# Variable_and_Constant.net
KiCad netlist of a schematic drawn in EAGLE
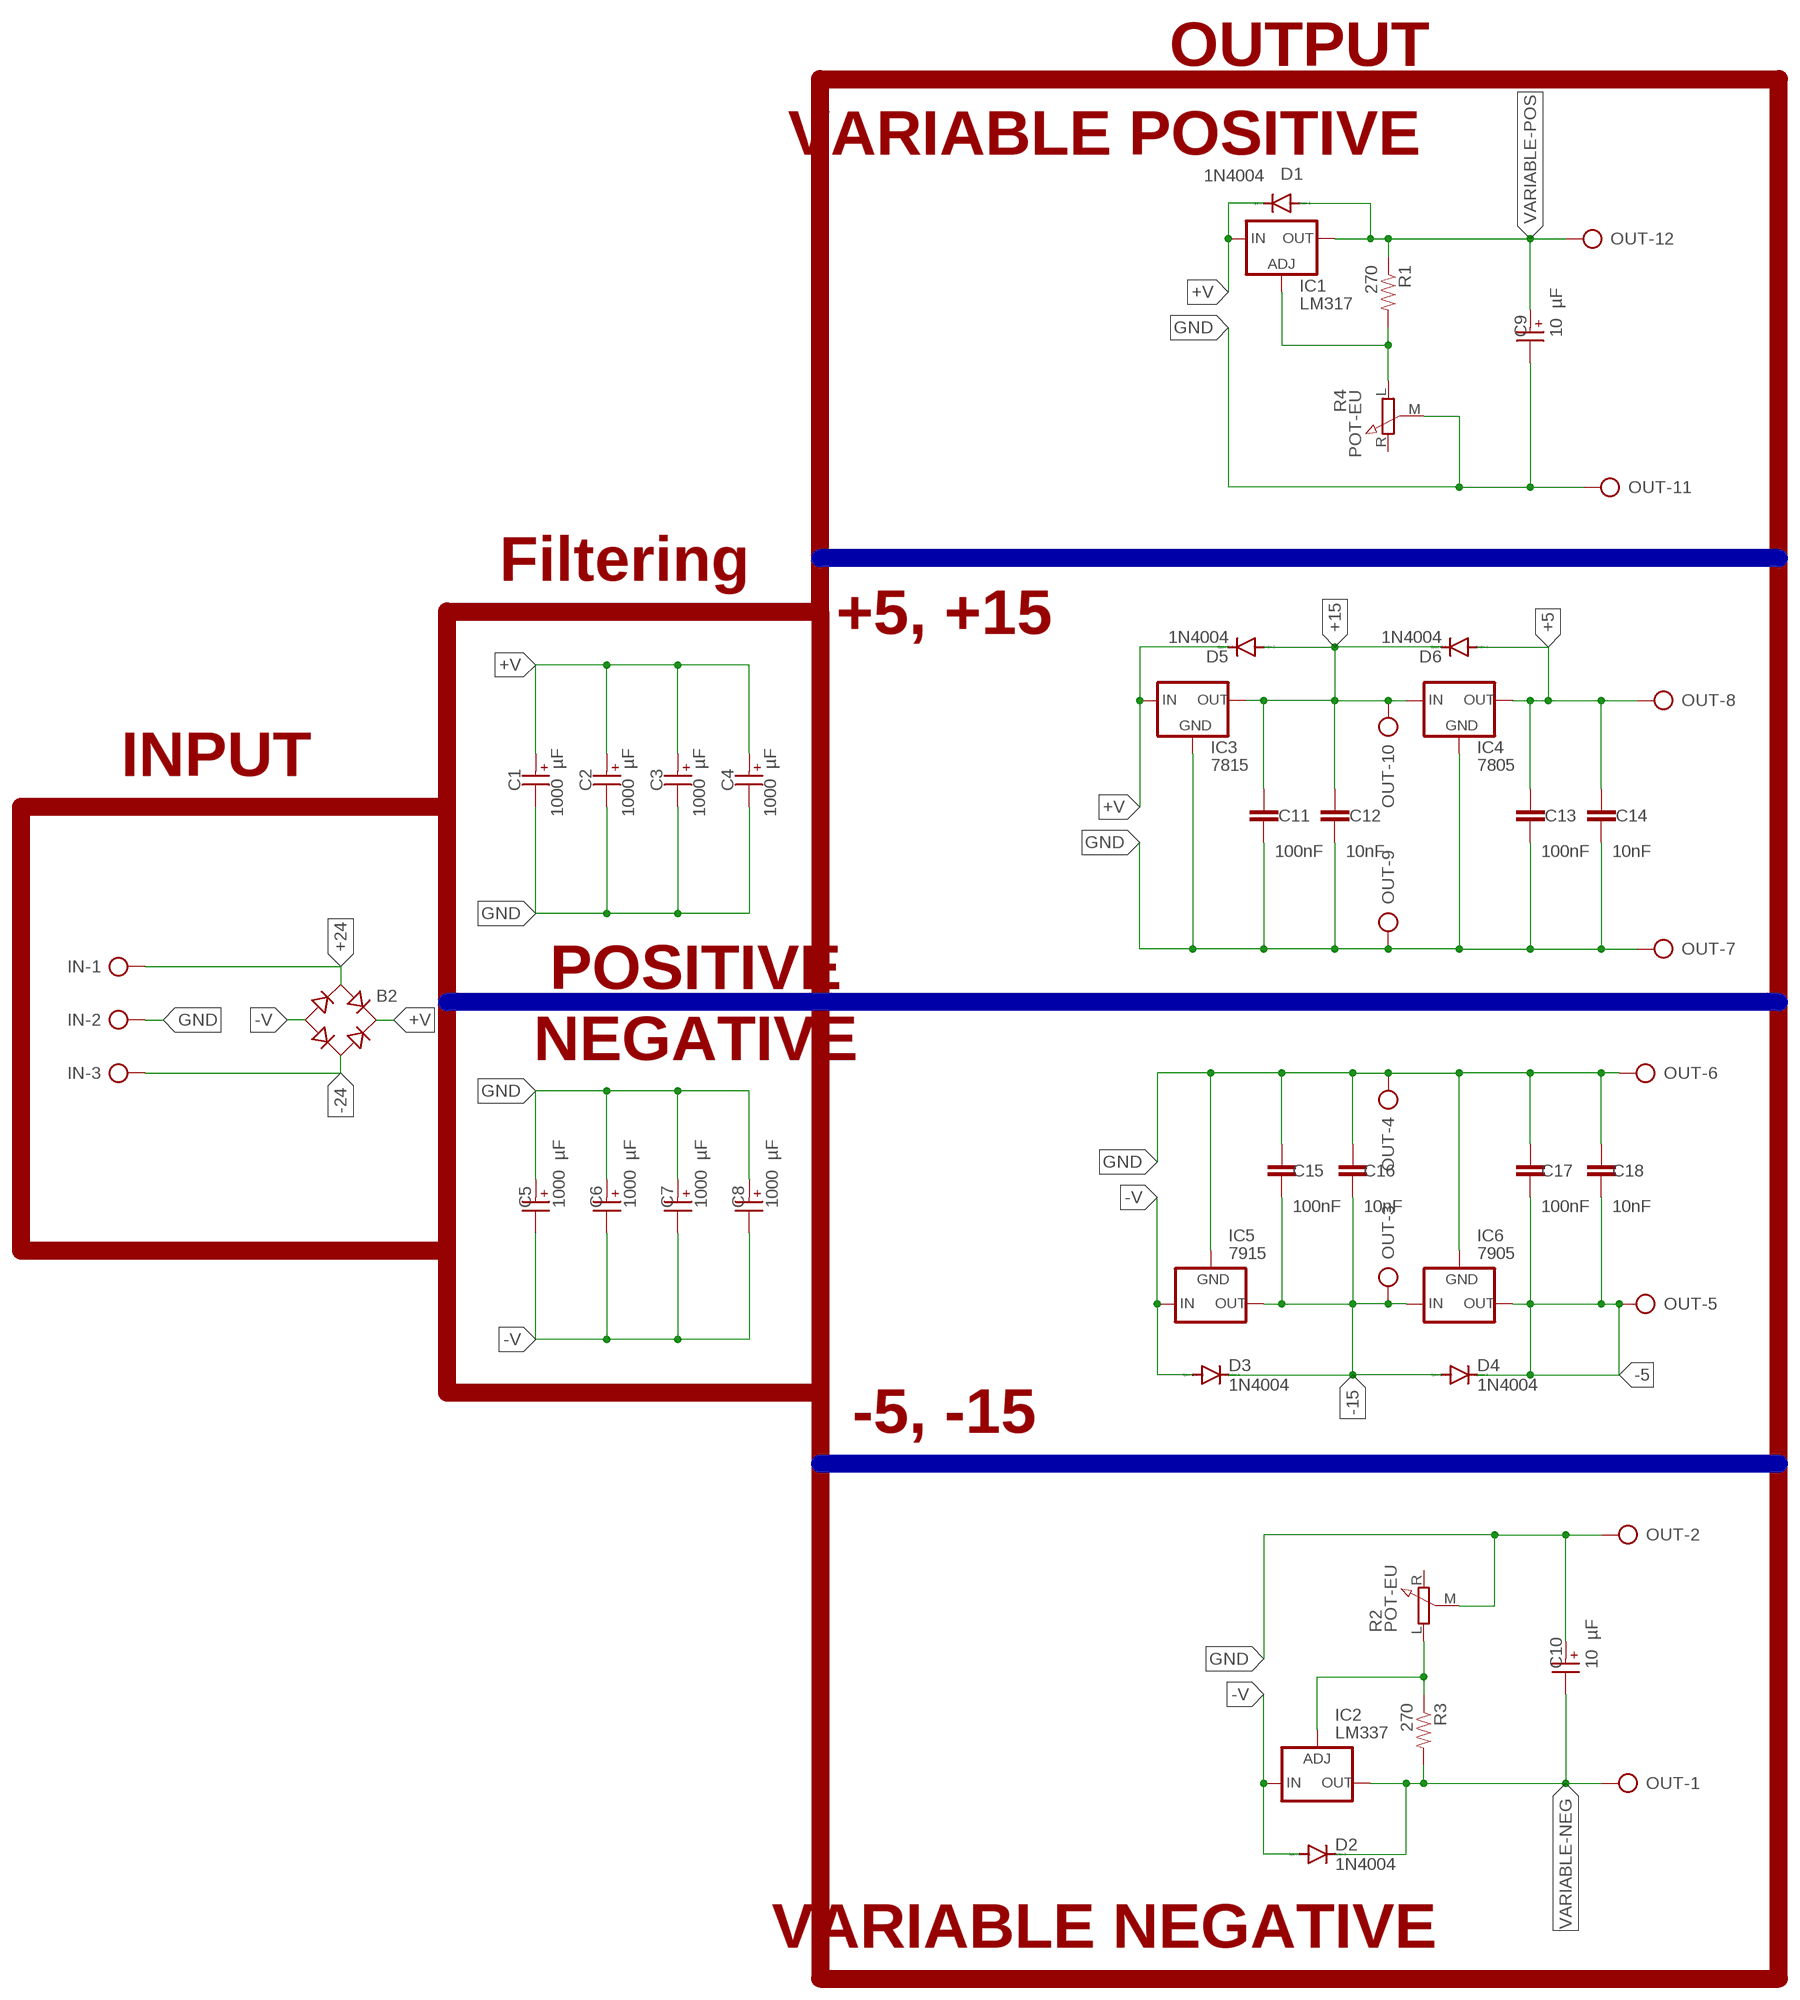
[diagram p0: schematic, sheet 1]

(export (version "E")
  (design (tool "Eeschema 10.0.6"))
  (components
    (comp (ref "B2")
      (value "RB1A")
      (footprint "eagle-import:RB1A")
      (libsource (lib "eagle-import") (part "RB1A"))
    )
    (comp (ref "C1")
      (value "1000 µF")
      (footprint "eagle-import:WCAP-ATG8_10X12.5(DXL)")
      (libsource (lib "eagle-import") (part "WCAP-ATG8_10X12.5_860010275016"))
    )
    (comp (ref "C2")
      (value "1000 µF")
      (footprint "eagle-import:WCAP-ATG8_10X12.5(DXL)")
      (libsource (lib "eagle-import") (part "WCAP-ATG8_10X12.5_860010275016"))
    )
    (comp (ref "C3")
      (value "1000 µF")
      (footprint "eagle-import:WCAP-ATG8_10X12.5(DXL)")
      (libsource (lib "eagle-import") (part "WCAP-ATG8_10X12.5_860010275016"))
    )
    (comp (ref "C4")
      (value "1000 µF")
      (footprint "eagle-import:WCAP-ATG8_10X12.5(DXL)")
      (libsource (lib "eagle-import") (part "WCAP-ATG8_10X12.5_860010275016"))
    )
    (comp (ref "C5")
      (value "1000 µF")
      (footprint "eagle-import:WCAP-ATG8_10X12.5(DXL)")
      (libsource (lib "eagle-import") (part "WCAP-ATG8_10X12.5_860010275016"))
    )
    (comp (ref "C6")
      (value "1000 µF")
      (footprint "eagle-import:WCAP-ATG8_10X12.5(DXL)")
      (libsource (lib "eagle-import") (part "WCAP-ATG8_10X12.5_860010275016"))
    )
    (comp (ref "C7")
      (value "1000 µF")
      (footprint "eagle-import:WCAP-ATG8_10X12.5(DXL)")
      (libsource (lib "eagle-import") (part "WCAP-ATG8_10X12.5_860010275016"))
    )
    (comp (ref "C8")
      (value "1000 µF")
      (footprint "eagle-import:WCAP-ATG8_10X12.5(DXL)")
      (libsource (lib "eagle-import") (part "WCAP-ATG8_10X12.5_860010275016"))
    )
    (comp (ref "C9")
      (value "10 µF")
      (footprint "eagle-import:WCAP-ATG8_5X11(DXL)")
      (libsource (lib "eagle-import") (part "WCAP-ATG8_5X11_860010772009"))
    )
    (comp (ref "C10")
      (value "10 µF")
      (footprint "eagle-import:WCAP-ATG8_5X11(DXL)")
      (libsource (lib "eagle-import") (part "WCAP-ATG8_5X11_860010772009"))
    )
    (comp (ref "C11")
      (value "100nF")
      (footprint "eagle-import:CAP-PTH-SMALL-KIT")
      (libsource (lib "eagle-import") (part "0.1UF-KIT-EZ-50V-20%"))
    )
    (comp (ref "C12")
      (value "10nF")
      (footprint "eagle-import:CAP-PTH-SMALL-KIT")
      (libsource (lib "eagle-import") (part "0.1UF-KIT-EZ-50V-20%"))
    )
    (comp (ref "C13")
      (value "100nF")
      (footprint "eagle-import:CAP-PTH-SMALL-KIT")
      (libsource (lib "eagle-import") (part "0.1UF-KIT-EZ-50V-20%"))
    )
    (comp (ref "C14")
      (value "10nF")
      (footprint "eagle-import:CAP-PTH-SMALL-KIT")
      (libsource (lib "eagle-import") (part "0.1UF-KIT-EZ-50V-20%"))
    )
    (comp (ref "C15")
      (value "100nF")
      (footprint "eagle-import:CAP-PTH-SMALL-KIT")
      (libsource (lib "eagle-import") (part "0.1UF-KIT-EZ-50V-20%"))
    )
    (comp (ref "C16")
      (value "10nF")
      (footprint "eagle-import:CAP-PTH-SMALL-KIT")
      (libsource (lib "eagle-import") (part "0.1UF-KIT-EZ-50V-20%"))
    )
    (comp (ref "C17")
      (value "100nF")
      (footprint "eagle-import:CAP-PTH-SMALL-KIT")
      (libsource (lib "eagle-import") (part "0.1UF-KIT-EZ-50V-20%"))
    )
    (comp (ref "C18")
      (value "10nF")
      (footprint "eagle-import:CAP-PTH-SMALL-KIT")
      (libsource (lib "eagle-import") (part "0.1UF-KIT-EZ-50V-20%"))
    )
    (comp (ref "D1")
      (value "1N4004")
      (footprint "eagle-import:DO41-10")
      (libsource (lib "eagle-import") (part "1N4004"))
    )
    (comp (ref "D2")
      (value "1N4004")
      (footprint "eagle-import:DO41-10")
      (libsource (lib "eagle-import") (part "1N4004"))
    )
    (comp (ref "D3")
      (value "1N4004")
      (footprint "eagle-import:DO41-10")
      (libsource (lib "eagle-import") (part "1N4004"))
    )
    (comp (ref "D4")
      (value "1N4004")
      (footprint "eagle-import:DO41-10")
      (libsource (lib "eagle-import") (part "1N4004"))
    )
    (comp (ref "D5")
      (value "1N4004")
      (footprint "eagle-import:DO41-10")
      (libsource (lib "eagle-import") (part "1N4004"))
    )
    (comp (ref "D6")
      (value "1N4004")
      (footprint "eagle-import:DO41-10")
      (libsource (lib "eagle-import") (part "1N4004"))
    )
    (comp (ref "IC1")
      (value "LM317")
      (footprint "eagle-import:317TS")
      (libsource (lib "eagle-import") (part "LM317TS"))
    )
    (comp (ref "IC2")
      (value "LM337")
      (footprint "eagle-import:337TS")
      (libsource (lib "eagle-import") (part "LM337TS"))
    )
    (comp (ref "IC3")
      (value "7815")
      (footprint "eagle-import:78XXS")
      (libsource (lib "eagle-import") (part "78XXS"))
    )
    (comp (ref "IC4")
      (value "7805")
      (footprint "eagle-import:78XXS")
      (libsource (lib "eagle-import") (part "78XXS"))
    )
    (comp (ref "IC5")
      (value "7915")
      (footprint "eagle-import:79XXS")
      (libsource (lib "eagle-import") (part "79XXS"))
    )
    (comp (ref "IC6")
      (value "7905")
      (footprint "eagle-import:79XXS")
      (libsource (lib "eagle-import") (part "79XXS"))
    )
    (comp (ref "IN")
      (value "AK500/3-H")
      (footprint "eagle-import:AK500_3-H")
      (libsource (lib "eagle-import") (part "AK500/3-H"))
    )
    (comp (ref "OUT")
      (value "AK500/12-H")
      (footprint "eagle-import:AK500_12-H")
      (libsource (lib "eagle-import") (part "AK500/12-H"))
    )
    (comp (ref "R1")
      (value "270")
      (footprint "eagle-import:AXIAL-0.3")
      (libsource (lib "eagle-import") (part "RESISTORAXIAL-0.3"))
    )
    (comp (ref "R2")
      (value "POT-EU")
      (footprint "eagle-import:RM-065")
      (libsource (lib "eagle-import") (part "POT-EU"))
    )
    (comp (ref "R3")
      (value "270")
      (footprint "eagle-import:AXIAL-0.3")
      (libsource (lib "eagle-import") (part "RESISTORAXIAL-0.3"))
    )
    (comp (ref "R4")
      (value "POT-EU")
      (footprint "eagle-import:RM-065")
      (libsource (lib "eagle-import") (part "POT-EU"))
    )
  )
  (nets
    (net (code "1") (name "+5") (class "Default")
      (node (ref "C13") (pin "1") (pinfunction "1_1") (pintype "passive"))
      (node (ref "C14") (pin "1") (pinfunction "1_1") (pintype "passive"))
      (node (ref "D6") (pin "A") (pinfunction "A_A") (pintype "passive"))
      (node (ref "IC4") (pin "OUT") (pinfunction "OUT_OUT") (pintype "passive"))
      (node (ref "OUT") (pin "8") (pinfunction "KL_8") (pintype "passive"))
    )
    (net (code "2") (name "+15") (class "Default")
      (node (ref "C11") (pin "1") (pinfunction "1_1") (pintype "passive"))
      (node (ref "C12") (pin "1") (pinfunction "1_1") (pintype "passive"))
      (node (ref "D5") (pin "A") (pinfunction "A_A") (pintype "passive"))
      (node (ref "D6") (pin "C") (pinfunction "C_C") (pintype "passive"))
      (node (ref "IC3") (pin "OUT") (pinfunction "OUT_OUT") (pintype "passive"))
      (node (ref "IC4") (pin "IN") (pinfunction "IN_IN") (pintype "input"))
      (node (ref "OUT") (pin "10") (pinfunction "KL_10") (pintype "passive"))
    )
    (net (code "3") (name "+24") (class "Default")
      (node (ref "B2") (pin "AC1") (pinfunction "AC1_AC1") (pintype "passive"))
      (node (ref "IN") (pin "1") (pinfunction "KL_1") (pintype "passive"))
    )
    (net (code "4") (name "+V") (class "Default")
      (node (ref "B2") (pin "+") (pinfunction "+_+") (pintype "passive"))
      (node (ref "C1") (pin "1") (pinfunction "+_1") (pintype "passive"))
      (node (ref "C2") (pin "1") (pinfunction "+_1") (pintype "passive"))
      (node (ref "C3") (pin "1") (pinfunction "+_1") (pintype "passive"))
      (node (ref "C4") (pin "1") (pinfunction "+_1") (pintype "passive"))
      (node (ref "D1") (pin "C") (pinfunction "C_C") (pintype "passive"))
      (node (ref "D5") (pin "C") (pinfunction "C_C") (pintype "passive"))
      (node (ref "IC1") (pin "3") (pinfunction "IN_3") (pintype "input"))
      (node (ref "IC3") (pin "IN") (pinfunction "IN_IN") (pintype "input"))
    )
    (net (code "5") (name "-5") (class "Default")
      (node (ref "C17") (pin "2") (pinfunction "2_2") (pintype "passive"))
      (node (ref "C18") (pin "2") (pinfunction "2_2") (pintype "passive"))
      (node (ref "D4") (pin "C") (pinfunction "C_C") (pintype "passive"))
      (node (ref "IC6") (pin "OUT") (pinfunction "OUT_OUT") (pintype "passive"))
      (node (ref "OUT") (pin "5") (pinfunction "KL_5") (pintype "passive"))
    )
    (net (code "6") (name "-15") (class "Default")
      (node (ref "C15") (pin "2") (pinfunction "2_2") (pintype "passive"))
      (node (ref "C16") (pin "2") (pinfunction "2_2") (pintype "passive"))
      (node (ref "D3") (pin "C") (pinfunction "C_C") (pintype "passive"))
      (node (ref "D4") (pin "A") (pinfunction "A_A") (pintype "passive"))
      (node (ref "IC5") (pin "OUT") (pinfunction "OUT_OUT") (pintype "passive"))
      (node (ref "IC6") (pin "IN") (pinfunction "IN_IN") (pintype "input"))
      (node (ref "OUT") (pin "3") (pinfunction "KL_3") (pintype "passive"))
    )
    (net (code "7") (name "-24") (class "Default")
      (node (ref "B2") (pin "AC2") (pinfunction "AC2_AC2") (pintype "passive"))
      (node (ref "IN") (pin "3") (pinfunction "KL_3") (pintype "passive"))
    )
    (net (code "8") (name "-V") (class "Default")
      (node (ref "B2") (pin "-") (pinfunction "-_-") (pintype "passive"))
      (node (ref "C5") (pin "2") (pinfunction "-_2") (pintype "passive"))
      (node (ref "C6") (pin "2") (pinfunction "-_2") (pintype "passive"))
      (node (ref "C7") (pin "2") (pinfunction "-_2") (pintype "passive"))
      (node (ref "C8") (pin "2") (pinfunction "-_2") (pintype "passive"))
      (node (ref "D2") (pin "A") (pinfunction "A_A") (pintype "passive"))
      (node (ref "D3") (pin "A") (pinfunction "A_A") (pintype "passive"))
      (node (ref "IC2") (pin "2") (pinfunction "IN_2") (pintype "input"))
      (node (ref "IC5") (pin "IN") (pinfunction "IN_IN") (pintype "input"))
    )
    (net (code "9") (name "GND") (class "Default")
      (node (ref "C1") (pin "2") (pinfunction "-_2") (pintype "passive"))
      (node (ref "C10") (pin "1") (pinfunction "+_1") (pintype "passive"))
      (node (ref "C11") (pin "2") (pinfunction "2_2") (pintype "passive"))
      (node (ref "C12") (pin "2") (pinfunction "2_2") (pintype "passive"))
      (node (ref "C13") (pin "2") (pinfunction "2_2") (pintype "passive"))
      (node (ref "C14") (pin "2") (pinfunction "2_2") (pintype "passive"))
      (node (ref "C15") (pin "1") (pinfunction "1_1") (pintype "passive"))
      (node (ref "C16") (pin "1") (pinfunction "1_1") (pintype "passive"))
      (node (ref "C17") (pin "1") (pinfunction "1_1") (pintype "passive"))
      (node (ref "C18") (pin "1") (pinfunction "1_1") (pintype "passive"))
      (node (ref "C2") (pin "2") (pinfunction "-_2") (pintype "passive"))
      (node (ref "C3") (pin "2") (pinfunction "-_2") (pintype "passive"))
      (node (ref "C4") (pin "2") (pinfunction "-_2") (pintype "passive"))
      (node (ref "C5") (pin "1") (pinfunction "+_1") (pintype "passive"))
      (node (ref "C6") (pin "1") (pinfunction "+_1") (pintype "passive"))
      (node (ref "C7") (pin "1") (pinfunction "+_1") (pintype "passive"))
      (node (ref "C8") (pin "1") (pinfunction "+_1") (pintype "passive"))
      (node (ref "C9") (pin "2") (pinfunction "-_2") (pintype "passive"))
      (node (ref "IC3") (pin "GND") (pinfunction "GND_GND") (pintype "input"))
      (node (ref "IC4") (pin "GND") (pinfunction "GND_GND") (pintype "input"))
      (node (ref "IC5") (pin "GND") (pinfunction "GND_GND") (pintype "input"))
      (node (ref "IC6") (pin "GND") (pinfunction "GND_GND") (pintype "input"))
      (node (ref "IN") (pin "2") (pinfunction "KL_2") (pintype "passive"))
      (node (ref "OUT") (pin "11") (pinfunction "KL_11") (pintype "passive"))
      (node (ref "OUT") (pin "2") (pinfunction "KL_2") (pintype "passive"))
      (node (ref "OUT") (pin "4") (pinfunction "KL_4") (pintype "passive"))
      (node (ref "OUT") (pin "6") (pinfunction "KL_6") (pintype "passive"))
      (node (ref "OUT") (pin "7") (pinfunction "KL_7") (pintype "passive"))
      (node (ref "OUT") (pin "9") (pinfunction "KL_9") (pintype "passive"))
      (node (ref "R2") (pin "M") (pinfunction "M_M") (pintype "passive"))
      (node (ref "R4") (pin "M") (pinfunction "M_M") (pintype "passive"))
    )
    (net (code "10") (name "Net-(IC1-ADJ)") (class "Default")
      (node (ref "IC1") (pin "1") (pinfunction "ADJ_1") (pintype "input"))
      (node (ref "R1") (pin "P$2") (pinfunction "2_P$2") (pintype "passive"))
      (node (ref "R4") (pin "L") (pinfunction "L_L") (pintype "passive"))
    )
    (net (code "11") (name "Net-(IC2-ADJ)") (class "Default")
      (node (ref "IC2") (pin "1") (pinfunction "ADJ_1") (pintype "input"))
      (node (ref "R2") (pin "L") (pinfunction "L_L") (pintype "passive"))
      (node (ref "R3") (pin "P$1") (pinfunction "1_P$1") (pintype "passive"))
    )
    (net (code "12") (name "VARIABLE-NEG") (class "Default")
      (node (ref "C10") (pin "2") (pinfunction "-_2") (pintype "passive"))
      (node (ref "D2") (pin "C") (pinfunction "C_C") (pintype "passive"))
      (node (ref "IC2") (pin "3") (pinfunction "OUT_3") (pintype "passive"))
      (node (ref "OUT") (pin "1") (pinfunction "KL_1") (pintype "passive"))
      (node (ref "R3") (pin "P$2") (pinfunction "2_P$2") (pintype "passive"))
    )
    (net (code "13") (name "VARIABLE-POS") (class "Default")
      (node (ref "C9") (pin "1") (pinfunction "+_1") (pintype "passive"))
      (node (ref "D1") (pin "A") (pinfunction "A_A") (pintype "passive"))
      (node (ref "IC1") (pin "2") (pinfunction "OUT_2") (pintype "passive"))
      (node (ref "OUT") (pin "12") (pinfunction "KL_12") (pintype "passive"))
      (node (ref "R1") (pin "P$1") (pinfunction "1_P$1") (pintype "passive"))
    )
    (net (code "14") (name "unconnected-(R2-PadR)") (class "Default")
      (node (ref "R2") (pin "R") (pinfunction "R_R") (pintype "passive"))
    )
    (net (code "15") (name "unconnected-(R4-PadR)") (class "Default")
      (node (ref "R4") (pin "R") (pinfunction "R_R") (pintype "passive"))
    )
  )
)
